# Audio.net
KiCad netlist of a schematic drawn in Altium Designer
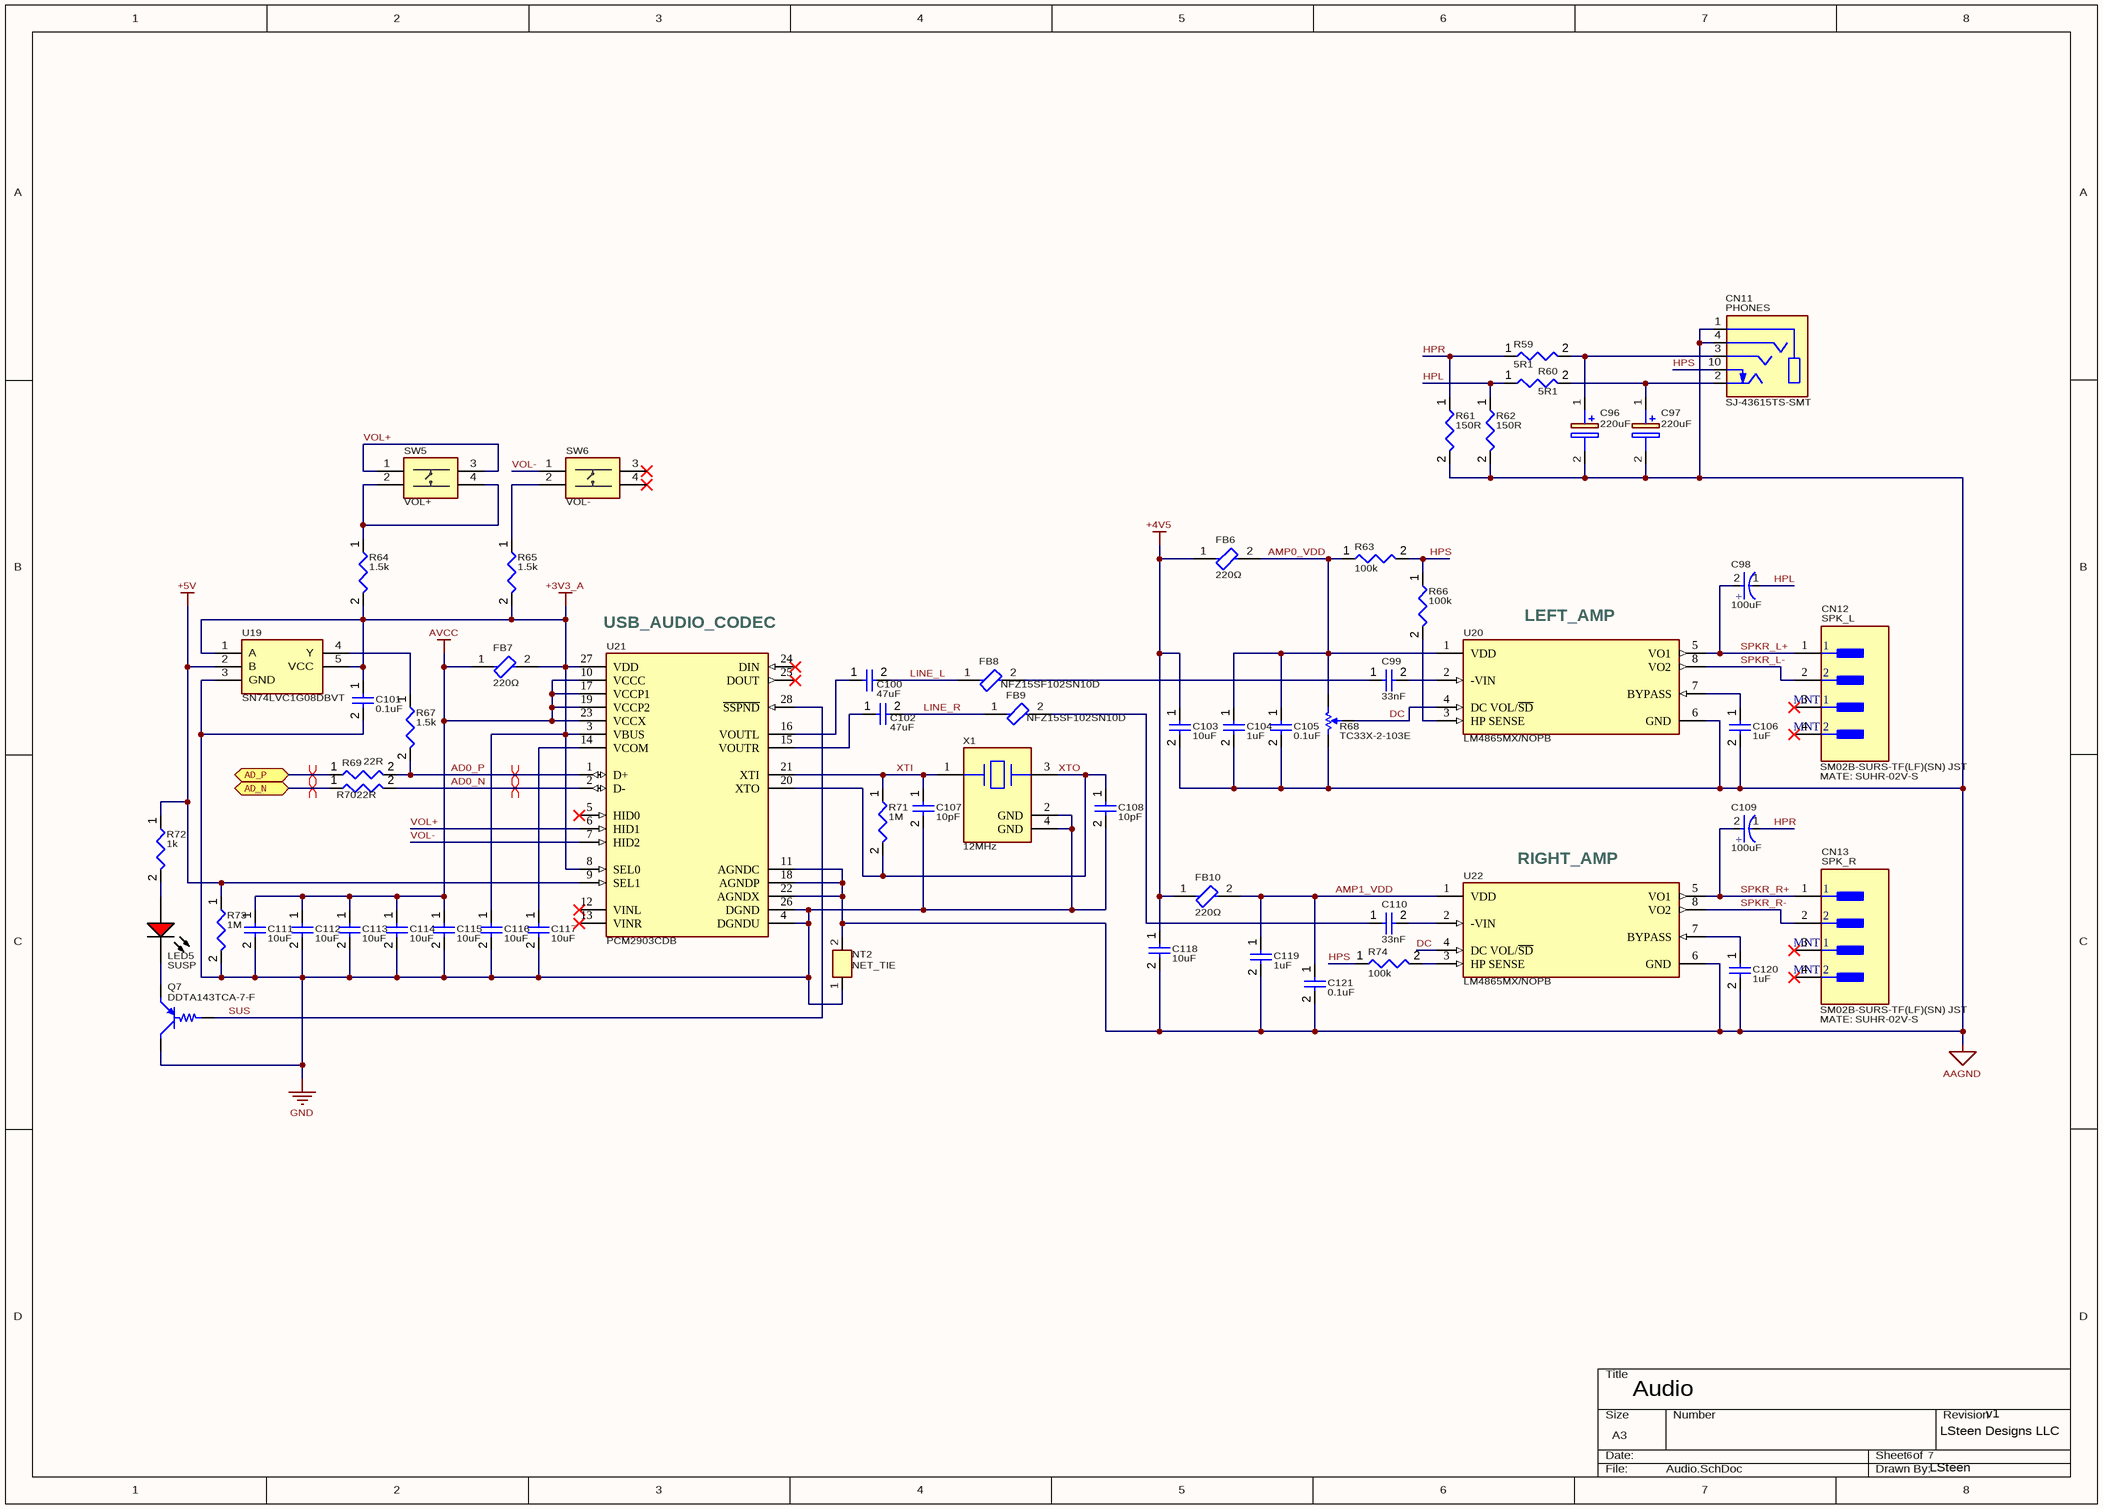
[diagram p0: Audio.SchDoc]

(export (version "E")
  (design (tool "Eeschema 10.0.6"))
  (components
    (comp (ref "C96")
      (value "220uF")
      (footprint "SamacSys:CAPPM6032X280N")
      (description "Capacitor Polarised")
      (fields (field (name "MANUFACTURER_PART_NUMBER") "TR3C227K6R3C0225"))
      (libsource (lib "SamacSys") (part "TR3C227K6R3C0225"))
    )
    (comp (ref "C97")
      (value "220uF")
      (footprint "SamacSys:CAPPM6032X280N")
      (description "Capacitor Polarised")
      (fields (field (name "MANUFACTURER_PART_NUMBER") "TR3C227K6R3C0225"))
      (libsource (lib "SamacSys") (part "TR3C227K6R3C0225"))
    )
    (comp (ref "C98")
      (value "100uF")
      (footprint "FP-CX-MFG")
      (description "CAP ALUM POLY 100UF 20% 6.3V SMD")
      (fields (field (name "VOLTAGE") "6.3V") (field (name "TOLERANCE") "20%"))
      (libsource (lib "Altium Content Vault") (part "a00bbbee19879c290e62620ae7e47b1"))
    )
    (comp (ref "C99")
      (value "33nF")
      (footprint "CAPC0603(1608)100_L")
      (description "Chip Capacitor, 33nF +/-20%, 10V, 0603, Thickness 1 mm")
      (fields (field (name "TOLERANCE") "10%"))
      (libsource (lib "Colorado Technical University") (part "CAP-NP-2"))
    )
    (comp (ref "C100")
      (value "47uF")
      (footprint "CAPC0603(1608)100_L")
      (description "Chip Capacitor, 47uF +/-20%, 10V, 0603, Thickness 1 mm")
      (fields (field (name "TOLERANCE") "10%"))
      (libsource (lib "Colorado Technical University") (part "CAP-NP-2"))
    )
    (comp (ref "C101")
      (value "0.1uF")
      (footprint "CAPC1005X56X25LL10T15")
      (description "Chip Capacitor, 0.1 uF, +/- 5%, 16 V, 0402 (1005 Metric)")
      (fields (field (name "TOLERANCE") "5%"))
      (libsource (lib "Colorado Technical University") (part "CAP-NP-2"))
    )
    (comp (ref "C102")
      (value "47uF")
      (footprint "CAPC0603(1608)100_L")
      (description "Chip Capacitor, 47uF +/-20%, 10V, 0603, Thickness 1 mm")
      (fields (field (name "TOLERANCE") "10%"))
      (libsource (lib "Colorado Technical University") (part "CAP-NP-2"))
    )
    (comp (ref "C103")
      (value "10uF")
      (footprint "CAPC0805(2012)145_L")
      (description "Chip Capacitor, 10µF +/-20%, 25V, 0805, Thickness 1.45 mm")
      (fields (field (name "TOLERANCE") "10%"))
      (libsource (lib "Colorado Technical University") (part "CAP-NP-2"))
    )
    (comp (ref "C104")
      (value "1uF")
      (footprint "CAPC0603(1608)100_L")
      (description "Chip Capacitor, 1uF +/-20%, 10V, 0603, Thickness 1 mm")
      (fields (field (name "TOLERANCE") "10%"))
      (libsource (lib "Colorado Technical University") (part "CAP-NP-2"))
    )
    (comp (ref "C105")
      (value "0.1uF")
      (footprint "CAPC1005X56X25LL10T15")
      (description "Chip Capacitor, 0.1 uF, +/- 5%, 16 V, 0402 (1005 Metric)")
      (fields (field (name "TOLERANCE") "5%"))
      (libsource (lib "Colorado Technical University") (part "CAP-NP-2"))
    )
    (comp (ref "C106")
      (value "1uF")
      (footprint "CAPC0603(1608)100_L")
      (description "Chip Capacitor, 1uF +/-20%, 10V, 0603, Thickness 1 mm")
      (fields (field (name "TOLERANCE") "10%"))
      (libsource (lib "Colorado Technical University") (part "CAP-NP-2"))
    )
    (comp (ref "C107")
      (value "10pF")
      (footprint "CAPC1005X56X25LL10T15")
      (description "Chip Capacitor, 10 pF, +/- 5%, 16 V, 0402 (1005 Metric)")
      (fields (field (name "TOLERANCE") "5%"))
      (libsource (lib "Colorado Technical University") (part "CAP-NP-2"))
    )
    (comp (ref "C108")
      (value "10pF")
      (footprint "CAPC1005X56X25LL10T15")
      (description "Chip Capacitor, 10 pF, +/- 5%, 16 V, 0402 (1005 Metric)")
      (fields (field (name "TOLERANCE") "5%"))
      (libsource (lib "Colorado Technical University") (part "CAP-NP-2"))
    )
    (comp (ref "C109")
      (value "100uF")
      (footprint "FP-CX-MFG")
      (description "CAP ALUM POLY 100UF 20% 6.3V SMD")
      (fields (field (name "VOLTAGE") "6.3V") (field (name "TOLERANCE") "20%"))
      (libsource (lib "Altium Content Vault") (part "a00bbbee19879c290e62620ae7e47b1"))
    )
    (comp (ref "C110")
      (value "33nF")
      (footprint "CAPC0603(1608)100_L")
      (description "Chip Capacitor, 33nF +/-20%, 10V, 0603, Thickness 1 mm")
      (fields (field (name "TOLERANCE") "10%"))
      (libsource (lib "Colorado Technical University") (part "CAP-NP-2"))
    )
    (comp (ref "C111")
      (value "10uF")
      (footprint "CAPC0805(2012)145_L")
      (description "Chip Capacitor, 10µF +/-20%, 25V, 0805, Thickness 1.45 mm")
      (fields (field (name "TOLERANCE") "10%"))
      (libsource (lib "Colorado Technical University") (part "CAP-NP-2"))
    )
    (comp (ref "C112")
      (value "10uF")
      (footprint "CAPC1005X56X25LL10T15")
      (description "Chip Capacitor, 10 uF, +/- 5%, 16 V, 0402 (1005 Metric)")
      (fields (field (name "TOLERANCE") "5%"))
      (libsource (lib "Colorado Technical University") (part "CAP-NP-2"))
    )
    (comp (ref "C113")
      (value "10uF")
      (footprint "CAPC1005X56X25LL10T15")
      (description "Chip Capacitor, 10 uF, +/- 5%, 16 V, 0402 (1005 Metric)")
      (fields (field (name "TOLERANCE") "5%"))
      (libsource (lib "Colorado Technical University") (part "CAP-NP-2"))
    )
    (comp (ref "C114")
      (value "10uF")
      (footprint "CAPC1005X56X25LL10T15")
      (description "Chip Capacitor, 10 uF, +/- 5%, 16 V, 0402 (1005 Metric)")
      (fields (field (name "TOLERANCE") "5%"))
      (libsource (lib "Colorado Technical University") (part "CAP-NP-2"))
    )
    (comp (ref "C115")
      (value "10uF")
      (footprint "CAPC1005X56X25LL10T15")
      (description "Chip Capacitor, 10 uF, +/- 5%, 16 V, 0402 (1005 Metric)")
      (fields (field (name "TOLERANCE") "5%"))
      (libsource (lib "Colorado Technical University") (part "CAP-NP-2"))
    )
    (comp (ref "C116")
      (value "10uF")
      (footprint "CAPC0603(1608)100_L")
      (description "Chip Capacitor, 10uF +/-20%, 10V, 0603, Thickness 1 mm")
      (fields (field (name "TOLERANCE") "10%"))
      (libsource (lib "Colorado Technical University") (part "CAP-NP-2"))
    )
    (comp (ref "C117")
      (value "10uF")
      (footprint "CAPC1005X56X25LL10T15")
      (description "Chip Capacitor, 10 uF, +/- 5%, 16 V, 0402 (1005 Metric)")
      (fields (field (name "TOLERANCE") "5%"))
      (libsource (lib "Colorado Technical University") (part "CAP-NP-2"))
    )
    (comp (ref "C118")
      (value "10uF")
      (footprint "CAPC0805(2012)145_L")
      (description "Chip Capacitor, 10µF +/-20%, 25V, 0805, Thickness 1.45 mm")
      (fields (field (name "TOLERANCE") "10%"))
      (libsource (lib "Colorado Technical University") (part "CAP-NP-2"))
    )
    (comp (ref "C119")
      (value "1uF")
      (footprint "CAPC0603(1608)100_L")
      (description "Chip Capacitor, 1uF +/-20%, 10V, 0603, Thickness 1 mm")
      (fields (field (name "TOLERANCE") "10%"))
      (libsource (lib "Colorado Technical University") (part "CAP-NP-2"))
    )
    (comp (ref "C120")
      (value "1uF")
      (footprint "CAPC0603(1608)100_L")
      (description "Chip Capacitor, 1uF +/-20%, 10V, 0603, Thickness 1 mm")
      (fields (field (name "TOLERANCE") "10%"))
      (libsource (lib "Colorado Technical University") (part "CAP-NP-2"))
    )
    (comp (ref "C121")
      (value "0.1uF")
      (footprint "CAPC1005X56X25LL10T15")
      (description "Chip Capacitor, 0.1 uF, +/- 5%, 16 V, 0402 (1005 Metric)")
      (fields (field (name "TOLERANCE") "5%"))
      (libsource (lib "Colorado Technical University") (part "CAP-NP-2"))
    )
    (comp (ref "CN11")
      (value "PHONES")
      (footprint "CUI_SJ-43615TS-SMT")
      (description "4 Conductor 3.5 mm Mid Mount SMT Audio Jack w/ Tip Switch")
      (fields (field (name "MP") "SJ-43615TS-SMT"))
      (libsource (lib "SJ-43615TS-SMT") (part "SJ-43615TS-SMT"))
    )
    (comp (ref "CN12")
      (value "SPK_L")
      (footprint "FP-SM02B-SURS-TF_LF_SN-MFG")
      (description "LCSC_CONN HEADER SMD R/A 2POS 0.8MM")
      (fields (field (name "MANUFACTURER PART NUMBER") "SM02B-SURS-TF(LF)(SN)"))
      (libsource (lib "Altium Content Vault") (part "6ebc6fc72a9fd5a6899c7600f385cff"))
    )
    (comp (ref "CN13")
      (value "SPK_R")
      (footprint "FP-SM02B-SURS-TF_LF_SN-MFG")
      (description "LCSC_CONN HEADER SMD R/A 2POS 0.8MM")
      (libsource (lib "Altium Content Vault") (part "6ebc6fc72a9fd5a6899c7600f385cff"))
    )
    (comp (ref "FB6")
      (value "220Ω")
      (footprint "FP-BLM18-0_15-t0_5-IPC_B")
      (description "Chip Ferrite Bead, 0603, 220Ω @ 100MHz, 25%, 0.04Ω, 2.5A")
      (libsource (lib "Altium Content Vault") (part "5f30dd21d616792df468990f7003faa"))
    )
    (comp (ref "FB7")
      (value "220Ω")
      (footprint "FP-BLM18-0_15-t0_5-IPC_B")
      (description "Chip Ferrite Bead, 0603, 220Ω @ 100MHz, 25%, 0.04Ω, 2.5A")
      (libsource (lib "Altium Content Vault") (part "5f30dd21d616792df468990f7003faa"))
    )
    (comp (ref "FB8")
      (value "NFZ15SF102SN10D")
      (footprint "FP-NFZ15S-IPC_A")
      (description "Ferrite Bead 1000Ω @ 100MHz ±25% 230mA 1.4Ω 0402 Paper T/R")
      (libsource (lib "Altium Content Vault") (part "5f30dd21d616792df468990f7003faa"))
    )
    (comp (ref "FB9")
      (value "NFZ15SF102SN10D")
      (footprint "FP-NFZ15S-IPC_A")
      (description "Ferrite Bead 1000Ω @ 100MHz ±25% 230mA 1.4Ω 0402 Paper T/R")
      (libsource (lib "Altium Content Vault") (part "5f30dd21d616792df468990f7003faa"))
    )
    (comp (ref "FB10")
      (value "220Ω")
      (footprint "FP-BLM18-0_15-t0_5-IPC_B")
      (description "Chip Ferrite Bead, 0603, 220Ω @ 100MHz, 25%, 0.04Ω, 2.5A")
      (libsource (lib "Altium Content Vault") (part "5f30dd21d616792df468990f7003faa"))
    )
    (comp (ref "LED5")
      (value "SUSP")
      (footprint "EVRL-0603-2_V")
      (description "Chip LED, Red, 5 V, 25 mA, -40 to 85 degC, 2-Pin SMD (0603), RoHS, Tape and Reel")
      (fields
        (field (name "MANUFACTURER") "Everlight Electronics")
        (field (name "MANUFACTURER PART NUMBER") "19-217/R6C-AL1M2VY/3T")
      )
      (libsource (lib "Altium Content Vault") (part "LED-RED-AK-2"))
    )
    (comp (ref "NT2") (value "NET_TIE") (footprint "NET_TIE1") (libsource (lib "Schlib1") (part "NET_TIE")))
    (comp (ref "Q7")
      (value "DDTA143TCA-7-F")
      (footprint "SOT96P240X120-3N")
      (description "PNP TRANSISTOR")
      (libsource (lib "Schlib1") (part "DDTA143TCA-7-F"))
    )
    (comp (ref "R59")
      (value "5R1")
      (footprint "RESC2013X50X35ML15T15")
      (description "Chip Resistor, 5.1 Ohm, +/- 1%, 125 mW, -55 to 155 degC, 0805 (2012 Metric)")
      (fields (field (name "TOLERANCE") "1%") (field (name "POWER") "125mW"))
      (libsource (lib "Colorado Technical University") (part "RES-2"))
    )
    (comp (ref "R60")
      (value "5R1")
      (footprint "RESC2013X50X35ML15T15")
      (description "Chip Resistor, 5.1 Ohm, +/- 1%, 125 mW, -55 to 155 degC, 0805 (2012 Metric)")
      (fields (field (name "TOLERANCE") "1%") (field (name "POWER") "125mW"))
      (libsource (lib "Colorado Technical University") (part "RES-2"))
    )
    (comp (ref "R61")
      (value "150R")
      (footprint "RESC0402(1005)_L")
      (description "Chip Resistor, 150 Ohms, +/-5 %, 63 mW, -55 to 155 degC, 0402")
      (fields (field (name "TOLERANCE") "5%") (field (name "POWER") "63mW"))
      (libsource (lib "Colorado Technical University") (part "RES-2"))
    )
    (comp (ref "R62")
      (value "150R")
      (footprint "RESC0402(1005)_L")
      (description "Chip Resistor, 150 Ohms, +/-5 %, 63 mW, -55 to 155 degC, 0402")
      (fields (field (name "TOLERANCE") "5%") (field (name "POWER") "63mW"))
      (libsource (lib "Colorado Technical University") (part "RES-2"))
    )
    (comp (ref "R63")
      (value "100k")
      (footprint "RESC0402(1005)_L")
      (description "Chip Resistor, 100 kOhms, +/-5 %, 63 mW, -55 to 155 degC, 0402")
      (fields (field (name "TOLERANCE") "5%") (field (name "POWER") "63mW"))
      (libsource (lib "Colorado Technical University") (part "RES-2"))
    )
    (comp (ref "R64")
      (value "1.5k")
      (footprint "RESC0402(1005)_L")
      (description "Chip Resistor, 1.5 kOhms, +/-5 %, 63 mW, -55 to 155 degC, 0402")
      (fields (field (name "TOLERANCE") "5%") (field (name "POWER") "63mW"))
      (libsource (lib "Colorado Technical University") (part "RES-2"))
    )
    (comp (ref "R65")
      (value "1.5k")
      (footprint "RESC0402(1005)_L")
      (description "Chip Resistor, 1.5 kOhms, +/-5 %, 63 mW, -55 to 155 degC, 0402")
      (fields (field (name "TOLERANCE") "5%") (field (name "POWER") "63mW"))
      (libsource (lib "Colorado Technical University") (part "RES-2"))
    )
    (comp (ref "R66")
      (value "100k")
      (footprint "RESC0402(1005)_L")
      (description "Chip Resistor, 100 kOhms, +/-5 %, 63 mW, -55 to 155 degC, 0402")
      (fields (field (name "TOLERANCE") "5%") (field (name "POWER") "63mW"))
      (libsource (lib "Colorado Technical University") (part "RES-2"))
    )
    (comp (ref "R67")
      (value "1.5k")
      (footprint "RESC0402(1005)_L")
      (description "Chip Resistor, 1.5 kOhms, +/-5 %, 63 mW, -55 to 155 degC, 0402")
      (fields (field (name "TOLERANCE") "5%") (field (name "POWER") "63mW"))
      (libsource (lib "Colorado Technical University") (part "RES-2"))
    )
    (comp (ref "R68")
      (value "TC33X-2-103E")
      (footprint "BOUR-TC33X-2_V")
      (description "Trimming Potentiometer, 10000 Ohm, -40 to 100 degC, 3-Pin SMD, RoHS, Tape and Reel")
      (fields (field (name "TOLERANCE") "25%") (field (name "MANUFACTURER") "Bourns"))
      (libsource (lib "Altium Content Vault") (part "RES-ADJ-3_A"))
    )
    (comp (ref "R69")
      (value "22R")
      (footprint "RESC0402(1005)_L")
      (description "Chip Resistor, 22 Ohms, +/-5 %, 63 mW, -55 to 155 degC, 0402")
      (fields (field (name "TOLERANCE") "5%") (field (name "POWER") "63mW"))
      (libsource (lib "Colorado Technical University") (part "RES-2"))
    )
    (comp (ref "R70")
      (value "22R")
      (footprint "RESC0402(1005)_L")
      (description "Chip Resistor, 22 Ohms, +/-5 %, 63 mW, -55 to 155 degC, 0402")
      (fields (field (name "TOLERANCE") "5%") (field (name "POWER") "63mW"))
      (libsource (lib "Colorado Technical University") (part "RES-2"))
    )
    (comp (ref "R71")
      (value "1M")
      (footprint "RESC0402(1005)_L")
      (description "Chip Resistor, 1 MOhms, +/-5 %, 63 mW, -55 to 155 degC, 0402")
      (fields (field (name "TOLERANCE") "5%") (field (name "POWER") "63mW"))
      (libsource (lib "Colorado Technical University") (part "RES-2"))
    )
    (comp (ref "R72")
      (value "1k")
      (footprint "RESC0402(1005)_L")
      (description "Chip Resistor, 1 kOhms, +/-5 %, 63 mW, -55 to 155 degC, 0402")
      (fields (field (name "TOLERANCE") "5%") (field (name "POWER") "63mW"))
      (libsource (lib "Colorado Technical University") (part "RES-2"))
    )
    (comp (ref "R73")
      (value "1M")
      (footprint "RESC0402(1005)_L")
      (description "Chip Resistor, 1 MOhms, +/-5 %, 63 mW, -55 to 155 degC, 0402")
      (fields (field (name "TOLERANCE") "5%") (field (name "POWER") "63mW"))
      (libsource (lib "Colorado Technical University") (part "RES-2"))
    )
    (comp (ref "R74")
      (value "100k")
      (footprint "RESC0402(1005)_L")
      (description "Chip Resistor, 100 kOhms, +/-5 %, 63 mW, -55 to 155 degC, 0402")
      (fields (field (name "TOLERANCE") "5%") (field (name "POWER") "63mW"))
      (libsource (lib "Colorado Technical University") (part "RES-2"))
    )
    (comp (ref "SW5")
      (value "VOL+")
      (footprint "SamacSys:APTCLGTVTR")
      (description "Switch")
      (fields
        (field (name "MANUFACTURER_PART_NUMBER") "APTCLGTVTR")
        (field (name "MOUSER PART NUMBER") "642-APTCLGTVTR")
      )
      (libsource (lib "SamacSys") (part "APTCLGTVTR"))
    )
    (comp (ref "SW6")
      (value "VOL-")
      (footprint "SamacSys:APTCLGTVTR")
      (description "Switch")
      (fields
        (field (name "MANUFACTURER_PART_NUMBER") "APTCLGTVTR")
        (field (name "MOUSER PART NUMBER") "642-APTCLGTVTR")
      )
      (libsource (lib "SamacSys") (part "APTCLGTVTR"))
    )
    (comp (ref "U19")
      (value "SN74LVC1G08DBVT")
      (footprint "SamacSys:SOT95P280X145-5N")
      (description "Integrated Circuit")
      (fields (field (name "MOUSER PART NUMBER") "595-SN74LVC1G08DBVT"))
      (libsource (lib "SamacSys") (part "SN74LVC1G08DBVT"))
    )
    (comp (ref "U20")
      (value "LM4865MX/NOPB")
      (footprint "FP-D0008A-IPC_C")
      (description "IC AMP CLASS AB MONO 1W 8SOIC")
      (libsource (lib "Altium Content Vault") (part "ab3269202495e4d39352532c15f18b6"))
    )
    (comp (ref "U21")
      (value "PCM2903CDB")
      (footprint "FP-DB0028A-IPC_A")
      (description "IC STERO AUD CODEC W/USB 28SSOP")
      (libsource (lib "Altium Content Vault") (part "e2d535d5cf0c7fcd44f2eec1acaa462"))
    )
    (comp (ref "U22")
      (value "LM4865MX/NOPB")
      (footprint "FP-D0008A-IPC_C")
      (description "IC AMP CLASS AB MONO 1W 8SOIC")
      (libsource (lib "Altium Content Vault") (part "ab3269202495e4d39352532c15f18b6"))
    )
    (comp (ref "X1")
      (value "12MHz")
      (footprint "FP-ABM8G-MFG")
      (description "Crystal 12MHz ±30ppm (Tol) ±30ppm (Stability) 10pF FUND 120Ω 4-Pin SMD T/R")
      (fields (field (name "TOLERANCE") "30ppm"))
      (libsource (lib "Altium Content Vault") (part "48e526d86b7f2615d98721063c72f49"))
    )
  )
  (nets
    (net (code "1") (name "+3V3_A") (class "Default")
      (node (ref "C101") (pin "1") (pinfunction "1_1") (pintype "passive"))
      (node (ref "C116") (pin "1") (pinfunction "1_1") (pintype "passive"))
      (node (ref "FB7") (pin "2") (pinfunction "2_2") (pintype "passive"))
      (node (ref "R64") (pin "2") (pinfunction "2_2") (pintype "passive"))
      (node (ref "R65") (pin "2") (pinfunction "2_2") (pintype "passive"))
      (node (ref "U19") (pin "1") (pinfunction "A_1") (pintype "passive"))
      (node (ref "U19") (pin "5") (pinfunction "VCC_5") (pintype "passive"))
      (node (ref "U21") (pin "27") (pinfunction "VDD_27") (pintype "power_in"))
      (node (ref "U21") (pin "3") (pinfunction "VBUS_3") (pintype "power_in"))
      (node (ref "U21") (pin "8") (pinfunction "SEL0_8") (pintype "input"))
    )
    (net (code "2") (name "+4V5") (class "Default")
      (node (ref "C103") (pin "1") (pinfunction "1_1") (pintype "passive"))
      (node (ref "C118") (pin "1") (pinfunction "1_1") (pintype "passive"))
      (node (ref "FB10") (pin "1") (pinfunction "1_1") (pintype "passive"))
      (node (ref "FB6") (pin "1") (pinfunction "1_1") (pintype "passive"))
    )
    (net (code "3") (name "+5V") (class "Default")
      (node (ref "R72") (pin "1") (pinfunction "1_1") (pintype "passive"))
      (node (ref "R73") (pin "1") (pinfunction "1_1") (pintype "passive"))
      (node (ref "U19") (pin "2") (pinfunction "B_2") (pintype "passive"))
      (node (ref "U21") (pin "9") (pinfunction "SEL1_9") (pintype "input"))
    )
    (net (code "4") (name "/AD0_N") (class "Default")
      (node (ref "R70") (pin "2") (pinfunction "2_2") (pintype "passive"))
      (node (ref "U21") (pin "2") (pinfunction "D-_2") (pintype "bidirectional"))
    )
    (net (code "5") (name "/AD0_P") (class "Default")
      (node (ref "R67") (pin "2") (pinfunction "2_2") (pintype "passive"))
      (node (ref "R69") (pin "2") (pinfunction "2_2") (pintype "passive"))
      (node (ref "U21") (pin "1") (pinfunction "D+_1") (pintype "bidirectional"))
    )
    (net (code "6") (name "/AD_N") (class "Default")
      (node (ref "R70") (pin "1") (pinfunction "1_1") (pintype "passive"))
    )
    (net (code "7") (name "/AD_P") (class "Default")
      (node (ref "R69") (pin "1") (pinfunction "1_1") (pintype "passive"))
    )
    (net (code "8") (name "/AMP0_VDD") (class "Default")
      (node (ref "C104") (pin "1") (pinfunction "1_1") (pintype "passive"))
      (node (ref "C105") (pin "1") (pinfunction "1_1") (pintype "passive"))
      (node (ref "FB6") (pin "2") (pinfunction "2_2") (pintype "passive"))
      (node (ref "R63") (pin "1") (pinfunction "1_1") (pintype "passive"))
      (node (ref "R68") (pin "1") (pinfunction "1_1") (pintype "passive"))
      (node (ref "U20") (pin "1") (pinfunction "VDD_1") (pintype "power_in"))
    )
    (net (code "9") (name "/AMP1_VDD") (class "Default")
      (node (ref "C119") (pin "1") (pinfunction "1_1") (pintype "passive"))
      (node (ref "C121") (pin "1") (pinfunction "1_1") (pintype "passive"))
      (node (ref "FB10") (pin "2") (pinfunction "2_2") (pintype "passive"))
      (node (ref "U22") (pin "1") (pinfunction "VDD_1") (pintype "power_in"))
    )
    (net (code "10") (name "/DC") (class "Default")
      (node (ref "R68") (pin "2") (pinfunction "2_2") (pintype "passive"))
      (node (ref "U20") (pin "4") (pinfunction "DC_VOL/~{SD}_4") (pintype "input"))
      (node (ref "U22") (pin "4") (pinfunction "DC_VOL/~{SD}_4") (pintype "input"))
    )
    (net (code "11") (name "/HPL") (class "Default")
      (node (ref "C98") (pin "1") (pinfunction "C_1") (pintype "passive"))
      (node (ref "R60") (pin "1") (pinfunction "1_1") (pintype "passive"))
      (node (ref "R62") (pin "1") (pinfunction "1_1") (pintype "passive"))
    )
    (net (code "12") (name "/HPR") (class "Default")
      (node (ref "C109") (pin "1") (pinfunction "C_1") (pintype "passive"))
      (node (ref "R59") (pin "1") (pinfunction "1_1") (pintype "passive"))
      (node (ref "R61") (pin "1") (pinfunction "1_1") (pintype "passive"))
    )
    (net (code "13") (name "/HPS") (class "Default")
      (node (ref "CN11") (pin "10") (pinfunction "TIP_SWITCH_10") (pintype "passive"))
      (node (ref "R63") (pin "2") (pinfunction "2_2") (pintype "passive"))
      (node (ref "R66") (pin "1") (pinfunction "1_1") (pintype "passive"))
      (node (ref "R74") (pin "1") (pinfunction "1_1") (pintype "passive"))
    )
    (net (code "14") (name "/LINE_L") (class "Default")
      (node (ref "C100") (pin "2") (pinfunction "2_2") (pintype "passive"))
      (node (ref "FB8") (pin "1") (pinfunction "1_1") (pintype "passive"))
    )
    (net (code "15") (name "/LINE_R") (class "Default")
      (node (ref "C102") (pin "2") (pinfunction "2_2") (pintype "passive"))
      (node (ref "FB9") (pin "1") (pinfunction "1_1") (pintype "passive"))
    )
    (net (code "16") (name "/SPKR_L+") (class "Default")
      (node (ref "C98") (pin "2") (pinfunction "A_2") (pintype "passive"))
      (node (ref "CN12") (pin "1") (pinfunction "1_1") (pintype "passive"))
      (node (ref "U20") (pin "5") (pinfunction "VO1_5") (pintype "output"))
    )
    (net (code "17") (name "/SPKR_L-") (class "Default")
      (node (ref "CN12") (pin "2") (pinfunction "2_2") (pintype "passive"))
      (node (ref "U20") (pin "8") (pinfunction "VO2_8") (pintype "output"))
    )
    (net (code "18") (name "/SPKR_R+") (class "Default")
      (node (ref "C109") (pin "2") (pinfunction "A_2") (pintype "passive"))
      (node (ref "CN13") (pin "1") (pinfunction "1_1") (pintype "passive"))
      (node (ref "U22") (pin "5") (pinfunction "VO1_5") (pintype "output"))
    )
    (net (code "19") (name "/SPKR_R-") (class "Default")
      (node (ref "CN13") (pin "2") (pinfunction "2_2") (pintype "passive"))
      (node (ref "U22") (pin "8") (pinfunction "VO2_8") (pintype "output"))
    )
    (net (code "20") (name "/SUS") (class "Default")
      (node (ref "Q7") (pin "1") (pinfunction "B_1") (pintype "passive"))
      (node (ref "U21") (pin "28") (pinfunction "~{SSPND}_28") (pintype "input"))
    )
    (net (code "21") (name "/VOL+") (class "Default")
      (node (ref "SW5") (pin "1") (pinfunction "1_1") (pintype "passive"))
      (node (ref "SW5") (pin "3") (pinfunction "3_3") (pintype "passive"))
      (node (ref "U21") (pin "6") (pinfunction "HID1_6") (pintype "input"))
    )
    (net (code "22") (name "/VOL-") (class "Default")
      (node (ref "SW6") (pin "1") (pinfunction "1_1") (pintype "passive"))
      (node (ref "U21") (pin "7") (pinfunction "HID2_7") (pintype "input"))
    )
    (net (code "23") (name "/XTI") (class "Default")
      (node (ref "C107") (pin "1") (pinfunction "1_1") (pintype "passive"))
      (node (ref "R71") (pin "1") (pinfunction "1_1") (pintype "passive"))
      (node (ref "U21") (pin "21") (pinfunction "XTI_21") (pintype "passive"))
      (node (ref "X1") (pin "1") (pinfunction "1_1") (pintype "passive"))
    )
    (net (code "24") (name "/XTO") (class "Default")
      (node (ref "C108") (pin "1") (pinfunction "1_1") (pintype "passive"))
      (node (ref "R71") (pin "2") (pinfunction "2_2") (pintype "passive"))
      (node (ref "U21") (pin "20") (pinfunction "XTO_20") (pintype "passive"))
      (node (ref "X1") (pin "3") (pinfunction "3_3") (pintype "passive"))
    )
    (net (code "25") (name "AAGND") (class "Default")
      (node (ref "C103") (pin "2") (pinfunction "2_2") (pintype "passive"))
      (node (ref "C104") (pin "2") (pinfunction "2_2") (pintype "passive"))
      (node (ref "C105") (pin "2") (pinfunction "2_2") (pintype "passive"))
      (node (ref "C106") (pin "2") (pinfunction "2_2") (pintype "passive"))
      (node (ref "C118") (pin "2") (pinfunction "2_2") (pintype "passive"))
      (node (ref "C119") (pin "2") (pinfunction "2_2") (pintype "passive"))
      (node (ref "C120") (pin "2") (pinfunction "2_2") (pintype "passive"))
      (node (ref "C121") (pin "2") (pinfunction "2_2") (pintype "passive"))
      (node (ref "C96") (pin "2") (pinfunction "-_2") (pintype "passive"))
      (node (ref "C97") (pin "2") (pinfunction "-_2") (pintype "passive"))
      (node (ref "CN11") (pin "1") (pinfunction "SLEEVE_1") (pintype "passive"))
      (node (ref "CN11") (pin "4") (pinfunction "RING2_4") (pintype "passive"))
      (node (ref "NT2") (pin "2") (pintype "passive"))
      (node (ref "R61") (pin "2") (pinfunction "2_2") (pintype "passive"))
      (node (ref "R62") (pin "2") (pinfunction "2_2") (pintype "passive"))
      (node (ref "R68") (pin "3") (pinfunction "3_3") (pintype "passive"))
      (node (ref "U20") (pin "6") (pinfunction "GND_6") (pintype "power_in"))
      (node (ref "U21") (pin "11") (pinfunction "AGNDC_11") (pintype "power_in"))
      (node (ref "U21") (pin "18") (pinfunction "AGNDP_18") (pintype "power_in"))
      (node (ref "U21") (pin "22") (pinfunction "AGNDX_22") (pintype "power_in"))
      (node (ref "U22") (pin "6") (pinfunction "GND_6") (pintype "power_in"))
    )
    (net (code "26") (name "AVCC") (class "Default")
      (node (ref "C111") (pin "1") (pinfunction "1_1") (pintype "passive"))
      (node (ref "C112") (pin "1") (pinfunction "1_1") (pintype "passive"))
      (node (ref "C113") (pin "1") (pinfunction "1_1") (pintype "passive"))
      (node (ref "C114") (pin "1") (pinfunction "1_1") (pintype "passive"))
      (node (ref "C115") (pin "1") (pinfunction "1_1") (pintype "passive"))
      (node (ref "FB7") (pin "1") (pinfunction "1_1") (pintype "passive"))
      (node (ref "U21") (pin "10") (pinfunction "VCCC_10") (pintype "power_in"))
      (node (ref "U21") (pin "17") (pinfunction "VCCP1_17") (pintype "passive"))
      (node (ref "U21") (pin "19") (pinfunction "VCCP2_19") (pintype "power_in"))
      (node (ref "U21") (pin "23") (pinfunction "VCCX_23") (pintype "power_in"))
    )
    (net (code "27") (name "GND") (class "Default")
      (node (ref "C101") (pin "2") (pinfunction "2_2") (pintype "passive"))
      (node (ref "C107") (pin "2") (pinfunction "2_2") (pintype "passive"))
      (node (ref "C108") (pin "2") (pinfunction "2_2") (pintype "passive"))
      (node (ref "C111") (pin "2") (pinfunction "2_2") (pintype "passive"))
      (node (ref "C112") (pin "2") (pinfunction "2_2") (pintype "passive"))
      (node (ref "C113") (pin "2") (pinfunction "2_2") (pintype "passive"))
      (node (ref "C114") (pin "2") (pinfunction "2_2") (pintype "passive"))
      (node (ref "C115") (pin "2") (pinfunction "2_2") (pintype "passive"))
      (node (ref "C116") (pin "2") (pinfunction "2_2") (pintype "passive"))
      (node (ref "C117") (pin "2") (pinfunction "2_2") (pintype "passive"))
      (node (ref "NT2") (pin "1") (pintype "passive"))
      (node (ref "Q7") (pin "3") (pinfunction "C_3") (pintype "passive"))
      (node (ref "R73") (pin "2") (pinfunction "2_2") (pintype "passive"))
      (node (ref "U19") (pin "3") (pinfunction "GND_3") (pintype "passive"))
      (node (ref "U21") (pin "26") (pinfunction "DGND_26") (pintype "power_in"))
      (node (ref "U21") (pin "4") (pinfunction "DGNDU_4") (pintype "power_in"))
      (node (ref "X1") (pin "2") (pinfunction "GND_2") (pintype "power_in"))
      (node (ref "X1") (pin "4") (pinfunction "GND_4") (pintype "power_in"))
    )
    (net (code "28") (name "Net-(C96-+)") (class "Default")
      (node (ref "C96") (pin "1") (pinfunction "+_1") (pintype "passive"))
      (node (ref "CN11") (pin "3") (pinfunction "RING1_3") (pintype "passive"))
      (node (ref "R59") (pin "2") (pinfunction "2_2") (pintype "passive"))
    )
    (net (code "29") (name "Net-(C97-+)") (class "Default")
      (node (ref "C97") (pin "1") (pinfunction "+_1") (pintype "passive"))
      (node (ref "CN11") (pin "2") (pinfunction "TIP_2") (pintype "passive"))
      (node (ref "R60") (pin "2") (pinfunction "2_2") (pintype "passive"))
    )
    (net (code "30") (name "Net-(C99-Pad1)") (class "Default")
      (node (ref "C99") (pin "1") (pinfunction "1_1") (pintype "passive"))
      (node (ref "FB8") (pin "2") (pinfunction "2_2") (pintype "passive"))
    )
    (net (code "31") (name "Net-(C110-Pad1)") (class "Default")
      (node (ref "C110") (pin "1") (pinfunction "1_1") (pintype "passive"))
      (node (ref "FB9") (pin "2") (pinfunction "2_2") (pintype "passive"))
    )
    (net (code "32") (name "Net-(LED5-A)") (class "Default")
      (node (ref "LED5") (pin "1") (pinfunction "A_1") (pintype "passive"))
      (node (ref "R72") (pin "2") (pinfunction "2_2") (pintype "passive"))
    )
    (net (code "33") (name "Net-(LED5-K)") (class "Default")
      (node (ref "LED5") (pin "2") (pinfunction "K_2") (pintype "passive"))
      (node (ref "Q7") (pin "2") (pinfunction "E_2") (pintype "passive"))
    )
    (net (code "34") (name "Net-(R64-Pad1)") (class "Default")
      (node (ref "R64") (pin "1") (pinfunction "1_1") (pintype "passive"))
      (node (ref "SW5") (pin "2") (pinfunction "2_2") (pintype "passive"))
      (node (ref "SW5") (pin "4") (pinfunction "4_4") (pintype "passive"))
    )
    (net (code "35") (name "Net-(R65-Pad1)") (class "Default")
      (node (ref "R65") (pin "1") (pinfunction "1_1") (pintype "passive"))
      (node (ref "SW6") (pin "2") (pinfunction "2_2") (pintype "passive"))
    )
    (net (code "36") (name "Net-(U19-Y)") (class "Default")
      (node (ref "R67") (pin "1") (pinfunction "1_1") (pintype "passive"))
      (node (ref "U19") (pin "4") (pinfunction "Y_4") (pintype "passive"))
    )
    (net (code "37") (name "Net-(U20--VIN)") (class "Default")
      (node (ref "C99") (pin "2") (pinfunction "2_2") (pintype "passive"))
      (node (ref "U20") (pin "2") (pinfunction "-VIN_2") (pintype "input"))
    )
    (net (code "38") (name "Net-(U20-BYPASS)") (class "Default")
      (node (ref "C106") (pin "1") (pinfunction "1_1") (pintype "passive"))
      (node (ref "U20") (pin "7") (pinfunction "BYPASS_7") (pintype "input"))
    )
    (net (code "39") (name "Net-(U20-HP_SENSE)") (class "Default")
      (node (ref "R66") (pin "2") (pinfunction "2_2") (pintype "passive"))
      (node (ref "U20") (pin "3") (pinfunction "HP_SENSE_3") (pintype "input"))
    )
    (net (code "40") (name "Net-(U21-VCOM)") (class "Default")
      (node (ref "C117") (pin "1") (pinfunction "1_1") (pintype "passive"))
      (node (ref "U21") (pin "14") (pinfunction "VCOM_14") (pintype "passive"))
    )
    (net (code "41") (name "Net-(U21-VOUTL)") (class "Default")
      (node (ref "C100") (pin "1") (pinfunction "1_1") (pintype "passive"))
      (node (ref "U21") (pin "16") (pinfunction "VOUTL_16") (pintype "passive"))
    )
    (net (code "42") (name "Net-(U21-VOUTR)") (class "Default")
      (node (ref "C102") (pin "1") (pinfunction "1_1") (pintype "passive"))
      (node (ref "U21") (pin "15") (pinfunction "VOUTR_15") (pintype "passive"))
    )
    (net (code "43") (name "Net-(U22--VIN)") (class "Default")
      (node (ref "C110") (pin "2") (pinfunction "2_2") (pintype "passive"))
      (node (ref "U22") (pin "2") (pinfunction "-VIN_2") (pintype "input"))
    )
    (net (code "44") (name "Net-(U22-BYPASS)") (class "Default")
      (node (ref "C120") (pin "1") (pinfunction "1_1") (pintype "passive"))
      (node (ref "U22") (pin "7") (pinfunction "BYPASS_7") (pintype "input"))
    )
    (net (code "45") (name "Net-(U22-HP_SENSE)") (class "Default")
      (node (ref "R74") (pin "2") (pinfunction "2_2") (pintype "passive"))
      (node (ref "U22") (pin "3") (pinfunction "HP_SENSE_3") (pintype "input"))
    )
    (net (code "46") (name "unconnected-(CN12-MNT_1-Pad3)") (class "Default")
      (node (ref "CN12") (pin "3") (pinfunction "MNT_1_3") (pintype "passive+no_connect"))
    )
    (net (code "47") (name "unconnected-(CN12-MNT_2-Pad4)") (class "Default")
      (node (ref "CN12") (pin "4") (pinfunction "MNT_2_4") (pintype "passive+no_connect"))
    )
    (net (code "48") (name "unconnected-(CN13-MNT_1-Pad3)") (class "Default")
      (node (ref "CN13") (pin "3") (pinfunction "MNT_1_3") (pintype "passive+no_connect"))
    )
    (net (code "49") (name "unconnected-(CN13-MNT_2-Pad4)") (class "Default")
      (node (ref "CN13") (pin "4") (pinfunction "MNT_2_4") (pintype "passive+no_connect"))
    )
    (net (code "50") (name "unconnected-(SW6-Pad3)") (class "Default")
      (node (ref "SW6") (pin "3") (pinfunction "3_3") (pintype "passive+no_connect"))
    )
    (net (code "51") (name "unconnected-(SW6-Pad4)") (class "Default")
      (node (ref "SW6") (pin "4") (pinfunction "4_4") (pintype "passive+no_connect"))
    )
    (net (code "52") (name "unconnected-(U21-DIN-Pad24)") (class "Default")
      (node (ref "U21") (pin "24") (pinfunction "DIN_24") (pintype "input+no_connect"))
    )
    (net (code "53") (name "unconnected-(U21-DOUT-Pad25)") (class "Default")
      (node (ref "U21") (pin "25") (pinfunction "DOUT_25") (pintype "output+no_connect"))
    )
    (net (code "54") (name "unconnected-(U21-HID0-Pad5)") (class "Default")
      (node (ref "U21") (pin "5") (pinfunction "HID0_5") (pintype "input+no_connect"))
    )
    (net (code "55") (name "unconnected-(U21-VINL-Pad12)") (class "Default")
      (node (ref "U21") (pin "12") (pinfunction "VINL_12") (pintype "passive+no_connect"))
    )
    (net (code "56") (name "unconnected-(U21-VINR-Pad13)") (class "Default")
      (node (ref "U21") (pin "13") (pinfunction "VINR_13") (pintype "passive+no_connect"))
    )
  )
)
